# SCH_FletchVR_2024-06-24.net
KiCad netlist of a schematic drawn in EasyEDA
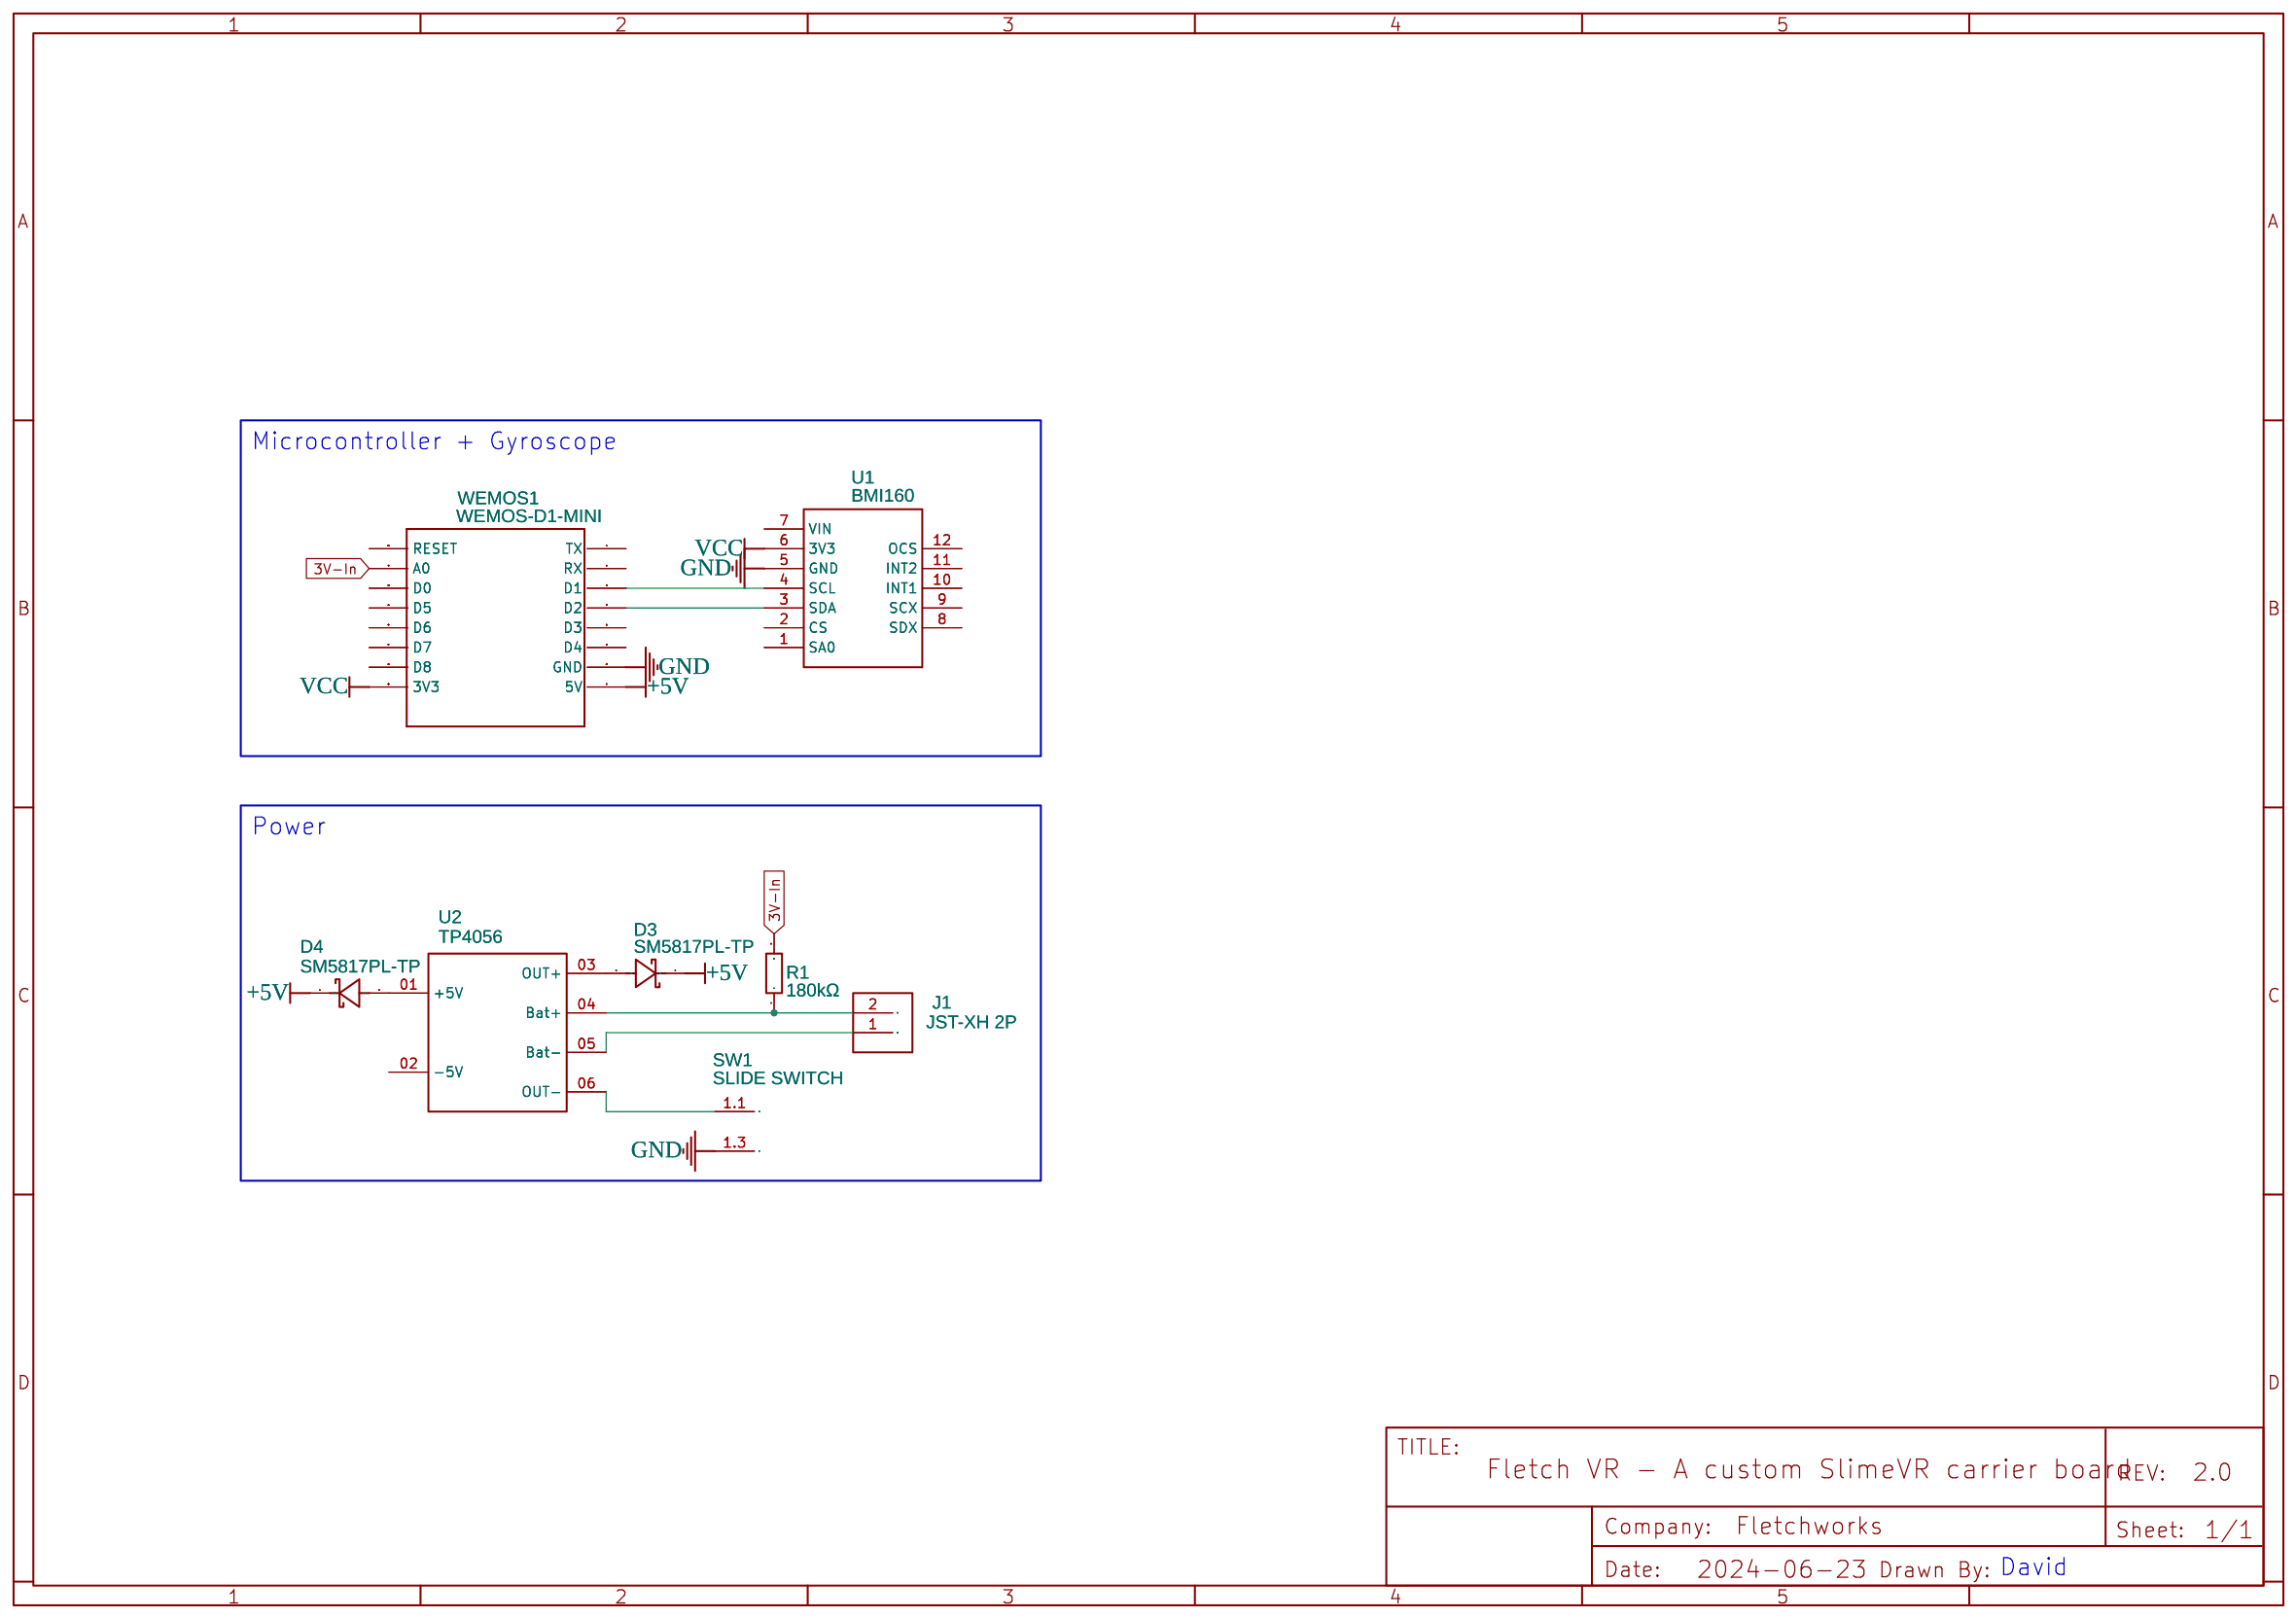
[diagram p0: schematic sheet]

(export (version "E")
  (design (tool "Eeschema 10.0.6"))
  (components
    (comp (ref "D3")
      (value "SM5817PL-TP")
      (fields (field (name "Manufacturer") "MCC(美微科)"))
      (libsource (lib "") (part "SM5817PL-TP_1"))
    )
    (comp (ref "D4")
      (value "SM5817PL-TP")
      (fields (field (name "Manufacturer") "MCC(美微科)"))
      (libsource (lib "") (part "SM5817PL-TP"))
    )
    (comp (ref "J1") (value "JST-XH 2P") (libsource (lib "") (part "JST-XH 2P")))
    (comp (ref "R1")
      (value "180kΩ")
      (fields
        (field (name "Manufacturer Part") "RMCF0402JT180K")
        (field (name "Manufacturer") "SEI(Stackpole Electronics Inc.)")
      )
      (libsource (lib "") (part "RMCF0402JT180K"))
    )
    (comp (ref "SW1")
      (value "SLIDE SWITCH")
      (fields (field (name "Manufacturer Part") "SS22F32"))
      (libsource (lib "") (part "SLIDE SWITCH 2P2T - SS22F32 PCB SLIME"))
    )
    (comp (ref "U1") (value "BMI160") (libsource (lib "") (part "BMI160")))
    (comp (ref "U2") (value "TP4056") (libsource (lib "") (part "TP4056 Symbole (modul)")))
    (comp (ref "WEMOS1") (value "WEMOS-D1-MINI") (libsource (lib "") (part "WEMOS-D1-MINI")))
  )
  (nets
    (net (code "1") (name "+5V") (class "Default")
      (node (ref "D3") (pin "1") (pinfunction "C_1") (pintype "unspecified"))
      (node (ref "D4") (pin "1") (pinfunction "C_1") (pintype "unspecified"))
      (node (ref "WEMOS1") (pin "5V") (pinfunction "5V_5V") (pintype "bidirectional"))
    )
    (net (code "2") (name "3V-In") (class "Default")
      (node (ref "R1") (pin "2") (pinfunction "2_2") (pintype "unspecified"))
      (node (ref "WEMOS1") (pin "A0") (pinfunction "A0_A0") (pintype "bidirectional"))
    )
    (net (code "3") (name "GND") (class "Default")
      (node (ref "SW1") (pin "1.3") (pinfunction "2_1.3") (pintype "unspecified"))
      (node (ref "U1") (pin "5") (pinfunction "GND_5") (pintype "unspecified"))
      (node (ref "WEMOS1") (pin "GND") (pinfunction "GND_GND") (pintype "bidirectional"))
    )
    (net (code "4") (name "Net-(D3-A)") (class "Default")
      (node (ref "D3") (pin "2") (pinfunction "A_2") (pintype "unspecified"))
      (node (ref "U2") (pin "03") (pinfunction "OUT+_03") (pintype "unspecified"))
    )
    (net (code "5") (name "Net-(D4-A)") (class "Default")
      (node (ref "D4") (pin "2") (pinfunction "A_2") (pintype "unspecified"))
      (node (ref "U2") (pin "01") (pinfunction "+5V_01") (pintype "unspecified"))
    )
    (net (code "6") (name "Net-(SW1-1)") (class "Default")
      (node (ref "SW1") (pin "1.1") (pinfunction "1_1.1") (pintype "unspecified"))
      (node (ref "U2") (pin "06") (pinfunction "OUT-_06") (pintype "unspecified"))
    )
    (net (code "7") (name "Net-(U1-SCL)") (class "Default")
      (node (ref "U1") (pin "4") (pinfunction "SCL_4") (pintype "unspecified"))
      (node (ref "WEMOS1") (pin "D1") (pinfunction "D1_D1") (pintype "bidirectional"))
    )
    (net (code "8") (name "Net-(U1-SDA)") (class "Default")
      (node (ref "U1") (pin "3") (pinfunction "SDA_3") (pintype "unspecified"))
      (node (ref "WEMOS1") (pin "D2") (pinfunction "D2_D2") (pintype "bidirectional"))
    )
    (net (code "9") (name "Net-(U2-Bat+)") (class "Default")
      (node (ref "J1") (pin "2") (pinfunction "2_2") (pintype "unspecified"))
      (node (ref "R1") (pin "1") (pinfunction "1_1") (pintype "unspecified"))
      (node (ref "U2") (pin "04") (pinfunction "Bat+_04") (pintype "unspecified"))
    )
    (net (code "10") (name "Net-(U2-Bat-)") (class "Default")
      (node (ref "J1") (pin "1") (pinfunction "1_1") (pintype "unspecified"))
      (node (ref "U2") (pin "05") (pinfunction "Bat-_05") (pintype "unspecified"))
    )
    (net (code "11") (name "VCC") (class "Default")
      (node (ref "U1") (pin "6") (pinfunction "3V3_6") (pintype "unspecified"))
      (node (ref "WEMOS1") (pin "3V3") (pinfunction "3V3_3V3") (pintype "bidirectional"))
    )
    (net (code "12") (name "unconnected-(U1-CS-Pad2)") (class "Default")
      (node (ref "U1") (pin "2") (pinfunction "CS_2") (pintype "unspecified"))
    )
    (net (code "13") (name "unconnected-(U1-INT1-Pad10)") (class "Default")
      (node (ref "U1") (pin "10") (pinfunction "INT1_10") (pintype "unspecified"))
    )
    (net (code "14") (name "unconnected-(U1-INT2-Pad11)") (class "Default")
      (node (ref "U1") (pin "11") (pinfunction "INT2_11") (pintype "unspecified"))
    )
    (net (code "15") (name "unconnected-(U1-OCS-Pad12)") (class "Default")
      (node (ref "U1") (pin "12") (pinfunction "OCS_12") (pintype "unspecified"))
    )
    (net (code "16") (name "unconnected-(U1-SA0-Pad1)") (class "Default")
      (node (ref "U1") (pin "1") (pinfunction "SA0_1") (pintype "unspecified"))
    )
    (net (code "17") (name "unconnected-(U1-SCX-Pad9)") (class "Default")
      (node (ref "U1") (pin "9") (pinfunction "SCX_9") (pintype "unspecified"))
    )
    (net (code "18") (name "unconnected-(U1-SDX-Pad8)") (class "Default")
      (node (ref "U1") (pin "8") (pinfunction "SDX_8") (pintype "unspecified"))
    )
    (net (code "19") (name "unconnected-(U1-VIN-Pad7)") (class "Default")
      (node (ref "U1") (pin "7") (pinfunction "VIN_7") (pintype "unspecified"))
    )
    (net (code "20") (name "unconnected-(U2--5V-Pad02)") (class "Default")
      (node (ref "U2") (pin "02") (pinfunction "-5V_02") (pintype "unspecified"))
    )
    (net (code "21") (name "unconnected-(WEMOS1-PadD0)") (class "Default")
      (node (ref "WEMOS1") (pin "D0") (pinfunction "D0_D0") (pintype "bidirectional"))
    )
    (net (code "22") (name "unconnected-(WEMOS1-PadD3)") (class "Default")
      (node (ref "WEMOS1") (pin "D3") (pinfunction "D3_D3") (pintype "bidirectional"))
    )
    (net (code "23") (name "unconnected-(WEMOS1-PadD4)") (class "Default")
      (node (ref "WEMOS1") (pin "D4") (pinfunction "D4_D4") (pintype "bidirectional"))
    )
    (net (code "24") (name "unconnected-(WEMOS1-PadD5)") (class "Default")
      (node (ref "WEMOS1") (pin "D5") (pinfunction "D5_D5") (pintype "bidirectional"))
    )
    (net (code "25") (name "unconnected-(WEMOS1-PadD6)") (class "Default")
      (node (ref "WEMOS1") (pin "D6") (pinfunction "D6_D6") (pintype "bidirectional"))
    )
    (net (code "26") (name "unconnected-(WEMOS1-PadD7)") (class "Default")
      (node (ref "WEMOS1") (pin "D7") (pinfunction "D7_D7") (pintype "bidirectional"))
    )
    (net (code "27") (name "unconnected-(WEMOS1-PadD8)") (class "Default")
      (node (ref "WEMOS1") (pin "D8") (pinfunction "D8_D8") (pintype "bidirectional"))
    )
    (net (code "28") (name "unconnected-(WEMOS1-PadRESET)") (class "Default")
      (node (ref "WEMOS1") (pin "RESET") (pinfunction "RESET_RESET") (pintype "bidirectional"))
    )
    (net (code "29") (name "unconnected-(WEMOS1-PadRX)") (class "Default")
      (node (ref "WEMOS1") (pin "RX") (pinfunction "RX_RX") (pintype "bidirectional"))
    )
    (net (code "30") (name "unconnected-(WEMOS1-PadTX)") (class "Default")
      (node (ref "WEMOS1") (pin "TX") (pinfunction "TX_TX") (pintype "bidirectional"))
    )
  )
)
